# PowerSupply.net
KiCad netlist of a schematic drawn in Altium Designer
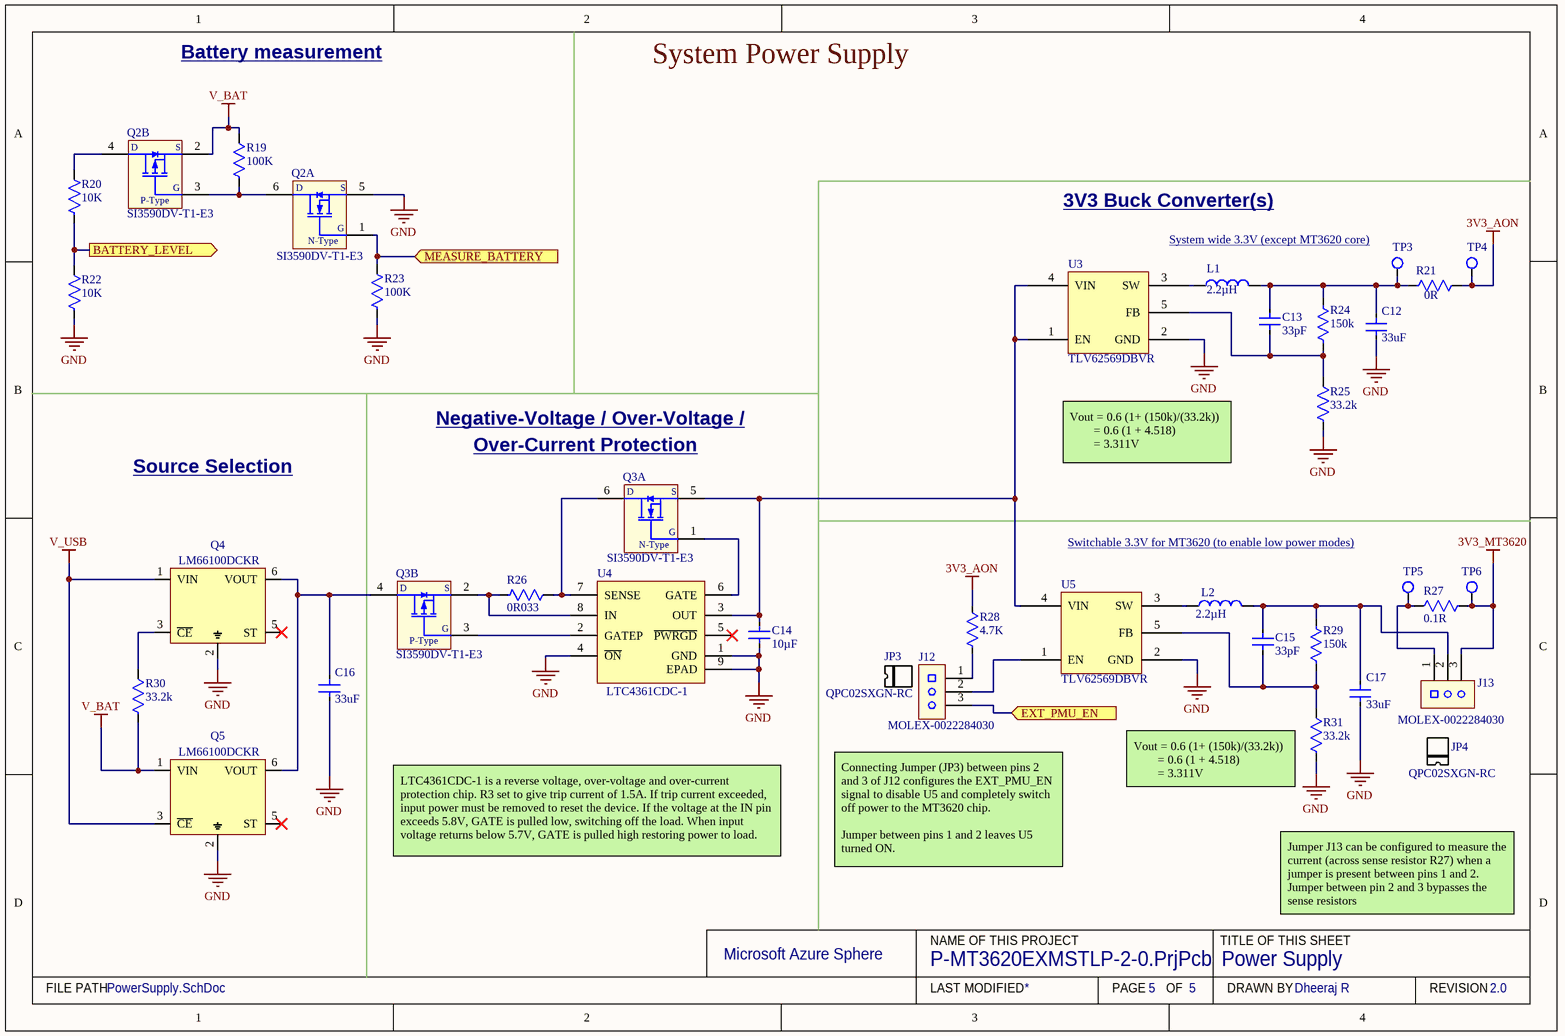
[diagram p0: PowerSupply.SchDoc]

(export (version "E")
  (design (tool "Eeschema 10.0.6"))
  (components
    (comp (ref "C12")
      (value "33uF")
      (footprint "TDK_0805")
      (description "CAP CER 33UF 10V X5R 0805")
      (fields
        (field (name "MANUFACTURER") "TDK")
        (field (name "MANUFACTURER PART NUMBER") "C2012X5R1A336M125AC")
      )
      (libsource (lib "TDK_Capacitor_C_0805") (part "33uF 0805 X5R 10V"))
    )
    (comp (ref "C13")
      (value "33pF")
      (footprint "0603_AVX")
      (fields
        (field (name "MANUFACTURER") "Kyocera AVX")
        (field (name "MANUFACTURER PART NUMBER") "0603YC330JAT2A")
        (field (name "TOLERANCE") "5%")
      )
      (libsource (lib "AVX") (part "0603YC330JAT2A"))
    )
    (comp (ref "C14")
      (value "10µF")
      (footprint "CAPC1608-EIA0603-1MM-MED")
      (description "CAP CER 10UF 25V 20% X5R 0603")
      (fields
        (field (name "MANUFACTURER") "TDK Corporation")
        (field (name "MANUFACTURER PART NUMBER") "C1608X5R1E106M080AC")
        (field (name "CAPACITANCE") "10µF")
      )
      (libsource (lib "TDK-Capacitor_C_0603") (part "10µF 0603 X5R 25V"))
    )
    (comp (ref "C15")
      (value "33pF")
      (footprint "0603_AVX")
      (fields
        (field (name "MANUFACTURER") "Kyocera AVX")
        (field (name "MANUFACTURER PART NUMBER") "0603YC330JAT2A")
        (field (name "TOLERANCE") "5%")
      )
      (libsource (lib "AVX") (part "0603YC330JAT2A"))
    )
    (comp (ref "C16")
      (value "33uF")
      (footprint "TDK_0805")
      (description "CAP CER 33UF 10V X5R 0805")
      (fields
        (field (name "MANUFACTURER") "TDK")
        (field (name "MANUFACTURER PART NUMBER") "C2012X5R1A336M125AC")
      )
      (libsource (lib "TDK_Capacitor_C_0805") (part "33uF 0805 X5R 10V"))
    )
    (comp (ref "C17")
      (value "33uF")
      (footprint "TDK_0805")
      (description "CAP CER 33UF 10V X5R 0805")
      (fields
        (field (name "MANUFACTURER") "TDK")
        (field (name "MANUFACTURER PART NUMBER") "C2012X5R1A336M125AC")
      )
      (libsource (lib "TDK_Capacitor_C_0805") (part "33uF 0805 X5R 10V"))
    )
    (comp (ref "J12")
      (value "MOLEX-0022284030")
      (footprint "0022284030")
      (description "CONN HEADER 3POS .100 VERT TIN")
      (fields
        (field (name "MANUFACTURER") "Molex, LLC")
        (field (name "MANUFACTURER PART NUMBER") "0022284030")
      )
      (libsource (lib "Molex") (part "MOLEX-0022284030"))
    )
    (comp (ref "J13")
      (value "MOLEX-0022284030")
      (footprint "0022284030")
      (description "CONN HEADER 3POS .100 VERT TIN")
      (fields
        (field (name "MANUFACTURER") "Molex, LLC")
        (field (name "MANUFACTURER PART NUMBER") "0022284030")
      )
      (libsource (lib "") (part "MOLEX-0022284030_1"))
    )
    (comp (ref "JP3")
      (value "QPC02SXGN-RC")
      (description "CONN JUMPER SHORTING .100\" GOLD")
      (fields (field (name "MANUFACTURER") "Sullins"))
      (libsource (lib "SullinsConnectorSolutions") (part "QPC02SXGN-RC"))
    )
    (comp (ref "JP4")
      (value "QPC02SXGN-RC")
      (description "CONN JUMPER SHORTING .100\" GOLD")
      (fields (field (name "MANUFACTURER") "Sullins"))
      (libsource (lib "SullinsConnectorSolutions") (part "QPC02SXGN-RC"))
    )
    (comp (ref "L1")
      (value "2.2µH")
      (footprint "NR3015T2R2M")
      (description "FIXED IND 2.2UH 1.5A 72 MOHM SMD")
      (fields
        (field (name "MANUFACTURER") "Taiyo Yuden")
        (field (name "MANUFACTURER PART NUMBER") "NR3015T2R2M")
      )
      (libsource (lib "TaiyoYuden ") (part "NR3015T2R2M"))
    )
    (comp (ref "L2")
      (value "2.2µH")
      (footprint "NR3015T2R2M")
      (description "FIXED IND 2.2UH 1.5A 72 MOHM SMD")
      (fields
        (field (name "MANUFACTURER") "Taiyo Yuden")
        (field (name "MANUFACTURER PART NUMBER") "NR3015T2R2M")
      )
      (libsource (lib "TaiyoYuden ") (part "NR3015T2R2M"))
    )
    (comp (ref "Q2")
      (value "SI3590DV-T1-E3")
      (footprint "SI3590DV-T1-E3")
      (description "MOSFET N&P-CH 30V (D-S)")
      (fields (field (name "MANUFACTURER") "Vishay Siliconix"))
      (libsource (lib "Vishay") (part "SI3590DV-T1-E3"))
    )
    (comp (ref "Q3")
      (value "SI3590DV-T1-E3")
      (footprint "SI3590DV-T1-E3")
      (description "MOSFET N&P-CH 30V (D-S)")
      (fields (field (name "MANUFACTURER") "Vishay Siliconix"))
      (libsource (lib "Vishay") (part "SI3590DV-T1-E3"))
    )
    (comp (ref "Q4")
      (value "LM66100DCKR")
      (footprint "TI-LM6610-SC-70")
      (description "1.5-V to 5.5-V, 1.5-A, 0.5-uA IQ ideal diode with Integrated FET 6-SC70 -40 to 105")
      (fields (field (name "MANUFACTURER") "Texas Instruments"))
      (libsource (lib "TexasInstruments") (part "LM66100DCKR"))
    )
    (comp (ref "Q5")
      (value "LM66100DCKR")
      (footprint "TI-LM6610-SC-70")
      (description "1.5-V to 5.5-V, 1.5-A, 0.5-uA IQ ideal diode with Integrated FET 6-SC70 -40 to 105")
      (fields (field (name "MANUFACTURER") "Texas Instruments"))
      (libsource (lib "TexasInstruments") (part "LM66100DCKR"))
    )
    (comp (ref "R19")
      (value "100K")
      (footprint "VISHAY-0603")
      (description "100K Ohm 0603 1% 0.1W(1/10W) 100ppm Paper T/R")
      (fields
        (field (name "MANUFACTURER") "Yageo")
        (field (name "MANUFACTURER PART NUMBER") "RC0603FR-07100KL")
      )
      (libsource (lib "Yageo") (part "RC0603FR-07100KL"))
    )
    (comp (ref "R20")
      (value "10K")
      (footprint "VISHAY-0603")
      (description "10K Ohm 0603 1% 1/10W ±100ppm/°C Molded SMD Paper T/R")
      (fields
        (field (name "MANUFACTURER") "Yageo")
        (field (name "MANUFACTURER PART NUMBER") "RC0603FR-0710KL")
      )
      (libsource (lib "Yageo") (part "RC0603FR-0710KL"))
    )
    (comp (ref "R21")
      (value "0R")
      (footprint "1608-EIA0603")
      (description "YAGEO         RC0603JR-070RL             RES, THICK FILM, 0R, 0.1W, 0603")
      (fields
        (field (name "MANUFACTURER") "Yageo")
        (field (name "MANUFACTURER PART NUMBER") "RC0603JR-070RL")
      )
      (libsource (lib "Yageo") (part "RC0603JR-070RL"))
    )
    (comp (ref "R22")
      (value "10K")
      (footprint "VISHAY-0603")
      (description "10K Ohm 0603 1% 1/10W ±100ppm/°C Molded SMD Paper T/R")
      (fields
        (field (name "MANUFACTURER") "Yageo")
        (field (name "MANUFACTURER PART NUMBER") "RC0603FR-0710KL")
      )
      (libsource (lib "Yageo") (part "RC0603FR-0710KL"))
    )
    (comp (ref "R23")
      (value "100K")
      (footprint "VISHAY-0603")
      (description "100K Ohm 0603 1% 0.1W(1/10W) 100ppm Paper T/R")
      (fields
        (field (name "MANUFACTURER") "Yageo")
        (field (name "MANUFACTURER PART NUMBER") "RC0603FR-07100KL")
      )
      (libsource (lib "Yageo") (part "RC0603FR-07100KL"))
    )
    (comp (ref "R24")
      (value "150k")
      (footprint "RC0603")
      (fields
        (field (name "MANUFACTURER") "Yageo")
        (field (name "MANUFACTURER PART NUMBER") "RC0603FR-07150KL")
        (field (name "TOLERANCE") "1%")
      )
      (libsource (lib "Yageo") (part "RC0603FR-07150KL"))
    )
    (comp (ref "R25")
      (value "33.2k")
      (footprint "RC0603")
      (description "33.2K OHM 1% 1/10W 0603")
      (fields
        (field (name "MANUFACTURER") "Yageo")
        (field (name "MANUFACTURER PART NUMBER") "RC0603FR-0733K2L")
      )
      (libsource (lib "Yageo") (part "RC0603FR-0733K2L"))
    )
    (comp (ref "R26")
      (value "0R033")
      (footprint "RC0603")
      (description "0.033 Ohm 0603 1% 0.1W(1/10W) ±1500ppm/C Epoxy Pad SMD Automotive T/R")
      (fields
        (field (name "MANUFACTURER") "Yageo")
        (field (name "MANUFACTURER PART NUMBER") "RL0603FR-070R033L")
      )
      (libsource (lib "Yageo") (part "RL0603FR-070R033L"))
    )
    (comp (ref "R27")
      (value "0.1R")
      (footprint "VISHAY-0603")
      (description "0.1 Ohm 0603 0.5% 0.20W Current Sense Rohs Compliant: Yes")
      (fields (field (name "MANUFACTURER") "Ohmite") (field (name "MANUFACTURER PART NUMBER") "KDV06DR100ET"))
      (libsource (lib "Ohmite") (part "KDV06DR100ET"))
    )
    (comp (ref "R28")
      (value "4.7K")
      (footprint "RC0603")
      (description "4.7K OHM 0603 1% 1/10W")
      (fields
        (field (name "MANUFACTURER") "Yageo")
        (field (name "MANUFACTURER PART NUMBER") "RC0603FR-074K7L")
      )
      (libsource (lib "Yageo") (part "RC0603FR-074K7L"))
    )
    (comp (ref "R29")
      (value "150k")
      (footprint "RC0603")
      (fields
        (field (name "MANUFACTURER") "Yageo")
        (field (name "MANUFACTURER PART NUMBER") "RC0603FR-07150KL")
        (field (name "TOLERANCE") "1%")
      )
      (libsource (lib "Yageo") (part "RC0603FR-07150KL"))
    )
    (comp (ref "R30")
      (value "33.2k")
      (footprint "RC0603")
      (description "33.2K OHM 1% 1/10W 0603")
      (fields
        (field (name "MANUFACTURER") "Yageo")
        (field (name "MANUFACTURER PART NUMBER") "RC0603FR-0733K2L")
      )
      (libsource (lib "Yageo") (part "RC0603FR-0733K2L"))
    )
    (comp (ref "R31")
      (value "33.2k")
      (footprint "RC0603")
      (description "33.2K OHM 1% 1/10W 0603")
      (fields
        (field (name "MANUFACTURER") "Yageo")
        (field (name "MANUFACTURER PART NUMBER") "RC0603FR-0733K2L")
      )
      (libsource (lib "Yageo") (part "RC0603FR-0733K2L"))
    )
    (comp (ref "TP3")
      (value "TestPointHole")
      (footprint "PTH1.27mm-0.9mm")
      (description "Test Point With Hole")
      (libsource (lib "generic") (part "TestPointHole"))
    )
    (comp (ref "TP4")
      (value "TestPointHole")
      (footprint "PTH1.27mm-0.9mm")
      (description "Test Point With Hole")
      (libsource (lib "generic") (part "TestPointHole"))
    )
    (comp (ref "TP5")
      (value "TestPointHole")
      (footprint "PTH1.27mm-0.9mm")
      (description "Test Point With Hole")
      (libsource (lib "generic") (part "TestPointHole"))
    )
    (comp (ref "TP6")
      (value "TestPointHole")
      (footprint "PTH1.27mm-0.9mm")
      (description "Test Point With Hole")
      (libsource (lib "generic") (part "TestPointHole"))
    )
    (comp (ref "U3")
      (value "TLV62569DBVR")
      (footprint "TI-SOT23-6")
      (description "Variable voltage buck converter")
      (fields (field (name "MANUFACTURER") "Texas Instruments"))
      (libsource (lib "TexasInstruments") (part "TLV62569DBVR"))
    )
    (comp (ref "U4")
      (value "LTC4361CDC-1")
      (footprint "LTC4361-1#TRPBF")
      (description "LINEAR TECHNOLOGY LTC4361CDC-1#TRMPBF IC, OVERVOLTAGE/CUR PROT, 8DFN")
      (fields
        (field (name "MANUFACTURER") "Linear Technology")
        (field (name "MANUFACTURER PART NUMBER") "LTC4361CDC-1#TRMPBF")
      )
      (libsource (lib "LinearTech") (part "LTC4361CDC-1#TRMPBF"))
    )
    (comp (ref "U5")
      (value "TLV62569DBVR")
      (footprint "TI-SOT23-6")
      (description "Variable voltage buck converter")
      (fields (field (name "MANUFACTURER") "Texas Instruments"))
      (libsource (lib "TexasInstruments") (part "TLV62569DBVR"))
    )
  )
  (nets
    (net (code "1") (name "/BATTERY_LEVEL") (class "Default")
      (node (ref "R20") (pin "1") (pinfunction "1_1") (pintype "passive"))
      (node (ref "R22") (pin "2") (pinfunction "2_2") (pintype "passive"))
    )
    (net (code "2") (name "/EXT_PMU_EN") (class "Default")
      (node (ref "J12") (pin "3") (pinfunction "3_3") (pintype "passive"))
    )
    (net (code "3") (name "/MEASURE_BATTERY") (class "Default")
      (node (ref "Q2") (pin "1") (pinfunction "G1_1") (pintype "passive"))
      (node (ref "R23") (pin "2") (pinfunction "2_2") (pintype "passive"))
    )
    (net (code "4") (name "3V3_AON") (class "Default")
      (node (ref "R21") (pin "2") (pinfunction "2_2") (pintype "passive"))
      (node (ref "R28") (pin "2") (pinfunction "2_2") (pintype "passive"))
      (node (ref "TP4") (pin "1") (pinfunction "1_1") (pintype "passive"))
    )
    (net (code "5") (name "3V3_MT3620") (class "Default")
      (node (ref "J13") (pin "3") (pinfunction "3_3") (pintype "passive"))
      (node (ref "R27") (pin "2") (pinfunction "2_2") (pintype "passive"))
      (node (ref "TP6") (pin "1") (pinfunction "1_1") (pintype "passive"))
    )
    (net (code "6") (name "GND") (class "Default")
      (node (ref "C12") (pin "1") (pinfunction "1_1") (pintype "passive"))
      (node (ref "C14") (pin "1") (pinfunction "1_1") (pintype "passive"))
      (node (ref "C16") (pin "1") (pinfunction "1_1") (pintype "passive"))
      (node (ref "C17") (pin "1") (pinfunction "1_1") (pintype "passive"))
      (node (ref "Q2") (pin "5") (pinfunction "S1_5") (pintype "passive"))
      (node (ref "Q4") (pin "2") (pinfunction "GND_2") (pintype "passive"))
      (node (ref "Q5") (pin "2") (pinfunction "GND_2") (pintype "passive"))
      (node (ref "R22") (pin "1") (pinfunction "1_1") (pintype "passive"))
      (node (ref "R23") (pin "1") (pinfunction "1_1") (pintype "passive"))
      (node (ref "R25") (pin "1") (pinfunction "1_1") (pintype "passive"))
      (node (ref "R31") (pin "1") (pinfunction "1_1") (pintype "passive"))
      (node (ref "U3") (pin "2") (pinfunction "GND_2") (pintype "passive"))
      (node (ref "U4") (pin "1") (pinfunction "GND_1") (pintype "passive"))
      (node (ref "U4") (pin "4") (pinfunction "~{ON}_4") (pintype "passive"))
      (node (ref "U4") (pin "9") (pinfunction "EPAD_9") (pintype "passive"))
      (node (ref "U5") (pin "2") (pinfunction "GND_2") (pintype "passive"))
    )
    (net (code "7") (name "Net-(C12-Pad2)") (class "Default")
      (node (ref "C12") (pin "2") (pinfunction "2_2") (pintype "passive"))
      (node (ref "C13") (pin "2") (pinfunction "2_2") (pintype "passive"))
      (node (ref "L1") (pin "2") (pinfunction "2_2") (pintype "passive"))
      (node (ref "R21") (pin "1") (pinfunction "1_1") (pintype "passive"))
      (node (ref "R24") (pin "2") (pinfunction "2_2") (pintype "passive"))
      (node (ref "TP3") (pin "1") (pinfunction "1_1") (pintype "passive"))
    )
    (net (code "8") (name "Net-(C15-Pad2)") (class "Default")
      (node (ref "C15") (pin "2") (pinfunction "2_2") (pintype "passive"))
      (node (ref "C17") (pin "2") (pinfunction "2_2") (pintype "passive"))
      (node (ref "J13") (pin "2") (pinfunction "2_2") (pintype "passive"))
      (node (ref "L2") (pin "2") (pinfunction "2_2") (pintype "passive"))
      (node (ref "R29") (pin "2") (pinfunction "2_2") (pintype "passive"))
    )
    (net (code "9") (name "Net-(J12-Pad1)") (class "Default")
      (node (ref "J12") (pin "1") (pinfunction "1_1") (pintype "passive"))
      (node (ref "R28") (pin "1") (pinfunction "1_1") (pintype "passive"))
    )
    (net (code "10") (name "Net-(J13-Pad1)") (class "Default")
      (node (ref "J13") (pin "1") (pinfunction "1_1") (pintype "passive"))
      (node (ref "R27") (pin "1") (pinfunction "1_1") (pintype "passive"))
      (node (ref "TP5") (pin "1") (pinfunction "1_1") (pintype "passive"))
    )
    (net (code "11") (name "Net-(Q2A-D1)") (class "Default")
      (node (ref "Q2") (pin "3") (pinfunction "G2_3") (pintype "passive"))
      (node (ref "Q2") (pin "6") (pinfunction "D1_6") (pintype "passive"))
      (node (ref "R19") (pin "1") (pinfunction "1_1") (pintype "passive"))
    )
    (net (code "12") (name "Net-(Q2B-D2)") (class "Default")
      (node (ref "Q2") (pin "4") (pinfunction "D2_4") (pintype "passive"))
      (node (ref "R20") (pin "2") (pinfunction "2_2") (pintype "passive"))
    )
    (net (code "13") (name "Net-(Q3A-D1)") (class "Default")
      (node (ref "Q3") (pin "6") (pinfunction "D1_6") (pintype "passive"))
      (node (ref "R26") (pin "2") (pinfunction "2_2") (pintype "passive"))
      (node (ref "U4") (pin "7") (pinfunction "SENSE_7") (pintype "passive"))
    )
    (net (code "14") (name "Net-(Q3A-G1)") (class "Default")
      (node (ref "Q3") (pin "1") (pinfunction "G1_1") (pintype "passive"))
      (node (ref "U4") (pin "6") (pinfunction "GATE_6") (pintype "passive"))
    )
    (net (code "15") (name "Net-(Q3A-S1)") (class "Default")
      (node (ref "C14") (pin "2") (pinfunction "2_2") (pintype "passive"))
      (node (ref "Q3") (pin "5") (pinfunction "S1_5") (pintype "passive"))
      (node (ref "U3") (pin "1") (pinfunction "EN_1") (pintype "passive"))
      (node (ref "U3") (pin "4") (pinfunction "VIN_4") (pintype "passive"))
      (node (ref "U4") (pin "3") (pinfunction "OUT_3") (pintype "passive"))
      (node (ref "U5") (pin "4") (pinfunction "VIN_4") (pintype "passive"))
    )
    (net (code "16") (name "Net-(Q3B-D2)") (class "Default")
      (node (ref "C16") (pin "2") (pinfunction "2_2") (pintype "passive"))
      (node (ref "Q3") (pin "4") (pinfunction "D2_4") (pintype "passive"))
      (node (ref "Q4") (pin "6") (pinfunction "VOUT_6") (pintype "passive"))
      (node (ref "Q5") (pin "6") (pinfunction "VOUT_6") (pintype "passive"))
    )
    (net (code "17") (name "Net-(Q3B-G2)") (class "Default")
      (node (ref "Q3") (pin "3") (pinfunction "G2_3") (pintype "passive"))
      (node (ref "U4") (pin "2") (pinfunction "GATEP_2") (pintype "passive"))
    )
    (net (code "18") (name "Net-(Q3B-S2)") (class "Default")
      (node (ref "Q3") (pin "2") (pinfunction "S2_2") (pintype "passive"))
      (node (ref "R26") (pin "1") (pinfunction "1_1") (pintype "passive"))
      (node (ref "U4") (pin "8") (pinfunction "IN_8") (pintype "passive"))
    )
    (net (code "19") (name "Net-(Q4-~{CE})") (class "Default")
      (node (ref "Q4") (pin "3") (pinfunction "~{CE}_3") (pintype "passive"))
      (node (ref "R30") (pin "2") (pinfunction "2_2") (pintype "passive"))
    )
    (net (code "20") (name "Net-(U3-FB)") (class "Default")
      (node (ref "C13") (pin "1") (pinfunction "1_1") (pintype "passive"))
      (node (ref "R24") (pin "1") (pinfunction "1_1") (pintype "passive"))
      (node (ref "R25") (pin "2") (pinfunction "2_2") (pintype "passive"))
      (node (ref "U3") (pin "5") (pinfunction "FB_5") (pintype "passive"))
    )
    (net (code "21") (name "Net-(U3-SW)") (class "Default")
      (node (ref "L1") (pin "1") (pinfunction "1_1") (pintype "passive"))
      (node (ref "U3") (pin "3") (pinfunction "SW_3") (pintype "passive"))
    )
    (net (code "22") (name "Net-(U5-EN)") (class "Default")
      (node (ref "J12") (pin "2") (pinfunction "2_2") (pintype "passive"))
      (node (ref "U5") (pin "1") (pinfunction "EN_1") (pintype "passive"))
    )
    (net (code "23") (name "Net-(U5-FB)") (class "Default")
      (node (ref "C15") (pin "1") (pinfunction "1_1") (pintype "passive"))
      (node (ref "R29") (pin "1") (pinfunction "1_1") (pintype "passive"))
      (node (ref "R31") (pin "2") (pinfunction "2_2") (pintype "passive"))
      (node (ref "U5") (pin "5") (pinfunction "FB_5") (pintype "passive"))
    )
    (net (code "24") (name "Net-(U5-SW)") (class "Default")
      (node (ref "L2") (pin "1") (pinfunction "1_1") (pintype "passive"))
      (node (ref "U5") (pin "3") (pinfunction "SW_3") (pintype "passive"))
    )
    (net (code "25") (name "V_BAT") (class "Default")
      (node (ref "Q2") (pin "2") (pinfunction "S2_2") (pintype "passive"))
      (node (ref "Q5") (pin "1") (pinfunction "VIN_1") (pintype "passive"))
      (node (ref "R19") (pin "2") (pinfunction "2_2") (pintype "passive"))
      (node (ref "R30") (pin "1") (pinfunction "1_1") (pintype "passive"))
    )
    (net (code "26") (name "V_USB") (class "Default")
      (node (ref "Q4") (pin "1") (pinfunction "VIN_1") (pintype "passive"))
      (node (ref "Q5") (pin "3") (pinfunction "~{CE}_3") (pintype "passive"))
    )
    (net (code "27") (name "unconnected-(Q4-NC-Pad4)") (class "Default")
      (node (ref "Q4") (pin "4") (pinfunction "NC_4") (pintype "passive"))
    )
    (net (code "28") (name "unconnected-(Q4-ST-Pad5)") (class "Default")
      (node (ref "Q4") (pin "5") (pinfunction "ST_5") (pintype "passive+no_connect"))
    )
    (net (code "29") (name "unconnected-(Q5-NC-Pad4)") (class "Default")
      (node (ref "Q5") (pin "4") (pinfunction "NC_4") (pintype "passive"))
    )
    (net (code "30") (name "unconnected-(Q5-ST-Pad5)") (class "Default")
      (node (ref "Q5") (pin "5") (pinfunction "ST_5") (pintype "passive+no_connect"))
    )
    (net (code "31") (name "unconnected-(U4-~{PWRGD}-Pad5)") (class "Default")
      (node (ref "U4") (pin "5") (pinfunction "~{PWRGD}_5") (pintype "passive+no_connect"))
    )
  )
)
